# main-power.net
KiCad netlist of a schematic drawn in Altium Designer
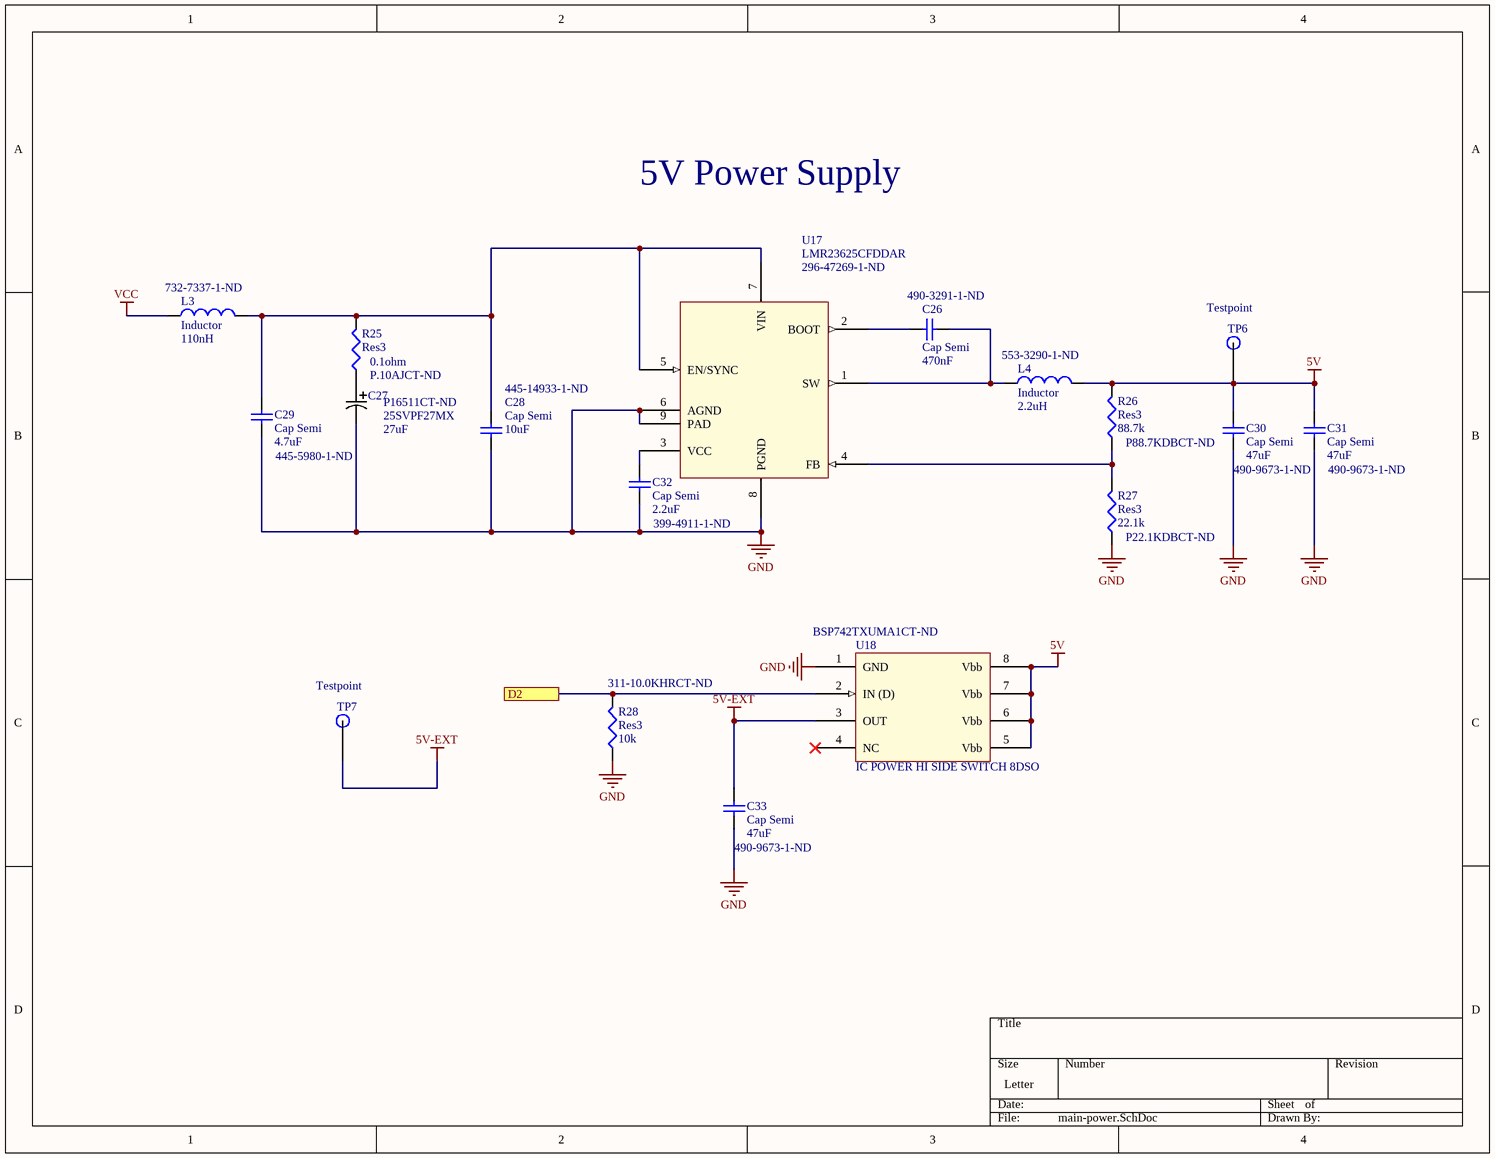
[diagram p0: main-power.SchDoc]

(export (version "E")
  (design (tool "Eeschema 10.0.6"))
  (components
    (comp (ref "C26")
      (value "Cap Semi")
      (footprint "1608[0603]")
      (description "Capacitor (Semiconductor SIM Model)")
      (fields
        (field (name "ALTIUM_VALUE") "470nF")
        (field (name "SUPPLIER PART NUMBER 1") "490-3291-1-ND")
        (field (name "MANUFACTURER") "Murata")
        (field (name "MANUFACTURER PART NUMBER") "GRM188R71E474KA12D")
        (field (name "PUBLISHER") "Altium Limited")
      )
      (libsource (lib "Miscellaneous Devices") (part "Cap Semi"))
    )
    (comp (ref "C27")
      (value "Part Number: 25SVPF27MX")
      (footprint "PCAP_SVP_B6")
      (description "No Description Available")
      (fields
        (field (name "MANUFACTURER_PART_NUMBER") "25SVPF27MX")
        (field (name "SUPPLIER PART NUMBER 1") "P16511CT-ND")
        (field (name "MANUFACTURER") "Panasonic")
        (field (name "MANUFACTURER PART NUMBER") "25SVPF27MX")
        (field (name "CAPACITANCE") "27uF")
        (field (name "COPYRIGHT") "Copyright (C) 2018 Accelerated Designs. All rights reserved")
      )
      (libsource (lib "Panasonic") (part "25SVPF27MX"))
    )
    (comp (ref "C28")
      (value "Cap Semi")
      (footprint "1210")
      (description "Capacitor (Semiconductor SIM Model)")
      (fields
        (field (name "ALTIUM_VALUE") "10uF")
        (field (name "SUPPLIER PART NUMBER 1") "445-14933-1-ND")
        (field (name "MANUFACTURER") "TDK")
        (field (name "MANUFACTURER PART NUMBER") "C3225X7R1H106M250AC")
        (field (name "PUBLISHER") "Altium Limited")
      )
      (libsource (lib "Miscellaneous Devices") (part "Cap Semi"))
    )
    (comp (ref "C29")
      (value "Cap Semi")
      (footprint "0805C")
      (description "Capacitor (Semiconductor SIM Model)")
      (fields
        (field (name "ALTIUM_VALUE") "4.7uF")
        (field (name "SUPPLIER PART NUMBER 1") "445-5980-1-ND")
        (field (name "MANUFACTURER") "TDK")
        (field (name "MANUFACTURER PART NUMBER") "C2012X5R1H475K125AB")
        (field (name "PUBLISHER") "Altium Limited")
      )
      (libsource (lib "Miscellaneous Devices") (part "Cap Semi"))
    )
    (comp (ref "C30")
      (value "Cap Semi")
      (footprint "C1206")
      (description "Capacitor (Semiconductor SIM Model)")
      (fields
        (field (name "ALTIUM_VALUE") "47uF")
        (field (name "SUPPLIER PART NUMBER 1") "490-9673-1-ND")
        (field (name "MANUFACTURER") "Murata")
        (field (name "MANUFACTURER PART NUMBER") "GRM31CR61A476KE15L")
        (field (name "PUBLISHER") "Altium Limited")
      )
      (libsource (lib "Miscellaneous Devices") (part "Cap Semi"))
    )
    (comp (ref "C31")
      (value "Cap Semi")
      (footprint "C1206")
      (description "Capacitor (Semiconductor SIM Model)")
      (fields
        (field (name "ALTIUM_VALUE") "47uF")
        (field (name "SUPPLIER PART NUMBER 1") "490-9673-1-ND")
        (field (name "MANUFACTURER") "Murata")
        (field (name "MANUFACTURER PART NUMBER") "GRM31CR61A476KE15L")
        (field (name "PUBLISHER") "Altium Limited")
      )
      (libsource (lib "Miscellaneous Devices") (part "Cap Semi"))
    )
    (comp (ref "C32")
      (value "Cap Semi")
      (footprint "1608[0603]")
      (description "Capacitor (Semiconductor SIM Model)")
      (fields
        (field (name "ALTIUM_VALUE") "2.2uF")
        (field (name "SUPPLIER PART NUMBER 1") "399-4911-1-ND")
        (field (name "MANUFACTURER") "KEMET")
        (field (name "MANUFACTURER PART NUMBER") "C0603C225K8PACTU")
        (field (name "PUBLISHER") "Altium Limited")
      )
      (libsource (lib "Miscellaneous Devices") (part "Cap Semi"))
    )
    (comp (ref "C33")
      (value "Cap Semi")
      (footprint "C1206")
      (description "Capacitor (Semiconductor SIM Model)")
      (fields
        (field (name "ALTIUM_VALUE") "47uF")
        (field (name "SUPPLIER PART NUMBER 1") "490-9673-1-ND")
        (field (name "MANUFACTURER") "Murata")
        (field (name "MANUFACTURER PART NUMBER") "GRM31CR61A476KE15L")
        (field (name "PUBLISHER") "Altium Limited")
      )
      (libsource (lib "Miscellaneous Devices") (part "Cap Semi"))
    )
    (comp (ref "L3")
      (value "Inductor")
      (footprint "inductor:74479899111")
      (fields
        (field (name "ALTIUM_VALUE") "110nH")
        (field (name "SUPPLIER PART NUMBER 1") "732-7337-1-ND")
        (field (name "MANUFACTURER") "Wurth Electronics")
        (field (name "MANUFACTURER PART NUMBER") "74479899111")
        (field (name "TOLERANCE") "20%")
        (field (name "PUBLISHER") "Altium Limited")
      )
      (libsource (lib "Miscellaneous Devices") (part "Inductor"))
    )
    (comp (ref "L4")
      (value "Inductor")
      (footprint "PA4332.222NLT")
      (fields
        (field (name "ALTIUM_VALUE") "2.2uH")
        (field (name "SUPPLIER PART NUMBER 1") "553-3290-1-ND")
        (field (name "MANUFACTURER") "Pulse Electronics")
        (field (name "MANUFACTURER PART NUMBER") "PA4332.222NLT")
        (field (name "TOLERANCE") "20%")
        (field (name "PUBLISHER") "Altium Limited")
      )
      (libsource (lib "Miscellaneous Devices") (part "Inductor"))
    )
    (comp (ref "R25")
      (value "Res3")
      (footprint "J1-0603")
      (description "Resistor")
      (fields
        (field (name "ALTIUM_VALUE") "0.1ohm")
        (field (name "SUPPLIER PART NUMBER 1") "P.10AJCT-ND")
        (field (name "MANUFACTURER") "Panasonic")
        (field (name "MANUFACTURER PART NUMBER") "ERJ3RSFR10V")
        (field (name "PUBLISHER") "Altium Limited")
      )
      (libsource (lib "Miscellaneous Devices") (part "Res3"))
    )
    (comp (ref "R26")
      (value "Res3")
      (footprint "J1-0603")
      (description "Resistor")
      (fields
        (field (name "ALTIUM_VALUE") "88.7k")
        (field (name "SUPPLIER PART NUMBER 1") "P88.7KDBCT-ND")
        (field (name "MANUFACTURER") "Panasonic")
        (field (name "MANUFACTURER PART NUMBER") "ERA3AEB8872V")
        (field (name "PUBLISHER") "Altium Limited")
      )
      (libsource (lib "Miscellaneous Devices") (part "Res3"))
    )
    (comp (ref "R27")
      (value "Res3")
      (footprint "J1-0603")
      (description "Resistor")
      (fields
        (field (name "ALTIUM_VALUE") "22.1k")
        (field (name "SUPPLIER PART NUMBER 1") "P22.1KDBCT-ND")
        (field (name "MANUFACTURER") "Panasonic")
        (field (name "MANUFACTURER PART NUMBER") "ERA-3AEB2212V")
        (field (name "PUBLISHER") "Altium Limited")
      )
      (libsource (lib "Miscellaneous Devices") (part "Res3"))
    )
    (comp (ref "R28")
      (value "Res3")
      (footprint "J1-0603")
      (description "Resistor")
      (fields
        (field (name "ALTIUM_VALUE") "10k")
        (field (name "SUPPLIER PART NUMBER 1") "311-10.0KHRCT-ND")
        (field (name "MANUFACTURER") "Yageo")
        (field (name "MANUFACTURER PART NUMBER") "RC0603FR-0710KL")
        (field (name "PUBLISHER") "Altium Limited")
      )
      (libsource (lib "Miscellaneous Devices") (part "Res3"))
    )
    (comp (ref "TP6")
      (value "Testpoint")
      (footprint "testpoint")
      (description "SMT Testpoint")
      (libsource (lib "testpoints") (part "SMT Testpoint"))
    )
    (comp (ref "TP7")
      (value "Testpoint")
      (footprint "testpoint")
      (description "SMT Testpoint")
      (libsource (lib "testpoints") (part "SMT Testpoint"))
    )
    (comp (ref "U17")
      (value "LMR23625CFDDAR")
      (footprint "DDA0008E_L")
      (fields
        (field (name "SUPPLIER PART NUMBER 1") "296-47269-1-ND")
        (field (name "MANUFACTURER") "Texas Instruments")
      )
      (libsource (lib "ti") (part "LMR23625CFDDAR"))
    )
    (comp (ref "U18")
      (value "IC POWER HI SIDE SWITCH 8DSO")
      (footprint "SOIC127P600-8N")
      (fields
        (field (name "SUPPLIER PART NUMBER 1") "BSP742TXUMA1CT-ND")
        (field (name "MANUFACTURER") "Infineon")
        (field (name "MANUFACTURER PART NUMBER") "BSP742TXUMA1")
      )
      (libsource (lib "Infineon") (part "BSP742TXUMA1"))
    )
  )
  (nets
    (net (code "1") (name "/D2") (class "Default")
      (node (ref "R28") (pin "2") (pinfunction "2_2") (pintype "passive"))
      (node (ref "U18") (pin "2") (pinfunction "IN_(D)_2") (pintype "input"))
    )
    (net (code "2") (name "5V") (class "Default")
      (node (ref "C30") (pin "2") (pinfunction "2_2") (pintype "passive"))
      (node (ref "C31") (pin "2") (pinfunction "2_2") (pintype "passive"))
      (node (ref "L4") (pin "2") (pinfunction "2_2") (pintype "passive"))
      (node (ref "R26") (pin "2") (pinfunction "2_2") (pintype "passive"))
      (node (ref "TP6") (pin "1") (pinfunction "1_1") (pintype "passive"))
      (node (ref "U18") (pin "5") (pinfunction "Vbb_5") (pintype "power_in"))
      (node (ref "U18") (pin "6") (pinfunction "Vbb_6") (pintype "power_in"))
      (node (ref "U18") (pin "7") (pinfunction "Vbb_7") (pintype "power_in"))
      (node (ref "U18") (pin "8") (pinfunction "Vbb_8") (pintype "power_in"))
    )
    (net (code "3") (name "5V-EXT") (class "Default")
      (node (ref "C33") (pin "2") (pinfunction "2_2") (pintype "passive"))
      (node (ref "TP7") (pin "1") (pinfunction "1_1") (pintype "passive"))
      (node (ref "U18") (pin "3") (pinfunction "OUT_3") (pintype "power_in"))
    )
    (net (code "4") (name "GND") (class "Default")
      (node (ref "C27") (pin "2") (pinfunction "2_2") (pintype "passive"))
      (node (ref "C28") (pin "1") (pinfunction "1_1") (pintype "passive"))
      (node (ref "C29") (pin "1") (pinfunction "1_1") (pintype "passive"))
      (node (ref "C30") (pin "1") (pinfunction "1_1") (pintype "passive"))
      (node (ref "C31") (pin "1") (pinfunction "1_1") (pintype "passive"))
      (node (ref "C32") (pin "1") (pinfunction "1_1") (pintype "passive"))
      (node (ref "C33") (pin "1") (pinfunction "1_1") (pintype "passive"))
      (node (ref "R27") (pin "1") (pinfunction "1_1") (pintype "passive"))
      (node (ref "R28") (pin "1") (pinfunction "1_1") (pintype "passive"))
      (node (ref "U17") (pin "6") (pinfunction "AGND_6") (pintype "power_in"))
      (node (ref "U17") (pin "8") (pinfunction "PGND_8") (pintype "power_in"))
      (node (ref "U17") (pin "9") (pinfunction "PAD_9") (pintype "power_in"))
      (node (ref "U18") (pin "1") (pinfunction "GND_1") (pintype "power_in"))
    )
    (net (code "5") (name "Net-(C27-Pad1)") (class "Default")
      (node (ref "C27") (pin "1") (pinfunction "1_1") (pintype "passive"))
      (node (ref "R25") (pin "1") (pinfunction "1_1") (pintype "passive"))
    )
    (net (code "6") (name "Net-(U17-BOOT)") (class "Default")
      (node (ref "C26") (pin "1") (pinfunction "1_1") (pintype "passive"))
      (node (ref "U17") (pin "2") (pinfunction "BOOT_2") (pintype "output"))
    )
    (net (code "7") (name "Net-(U17-EN{slash}SYNC)") (class "Default")
      (node (ref "C28") (pin "2") (pinfunction "2_2") (pintype "passive"))
      (node (ref "C29") (pin "2") (pinfunction "2_2") (pintype "passive"))
      (node (ref "L3") (pin "2") (pinfunction "2_2") (pintype "passive"))
      (node (ref "R25") (pin "2") (pinfunction "2_2") (pintype "passive"))
      (node (ref "U17") (pin "5") (pinfunction "EN/SYNC_5") (pintype "input"))
      (node (ref "U17") (pin "7") (pinfunction "VIN_7") (pintype "power_in"))
    )
    (net (code "8") (name "Net-(U17-FB)") (class "Default")
      (node (ref "R26") (pin "1") (pinfunction "1_1") (pintype "passive"))
      (node (ref "R27") (pin "2") (pinfunction "2_2") (pintype "passive"))
      (node (ref "U17") (pin "4") (pinfunction "FB_4") (pintype "input"))
    )
    (net (code "9") (name "Net-(U17-SW)") (class "Default")
      (node (ref "C26") (pin "2") (pinfunction "2_2") (pintype "passive"))
      (node (ref "L4") (pin "1") (pinfunction "1_1") (pintype "passive"))
      (node (ref "U17") (pin "1") (pinfunction "SW_1") (pintype "output"))
    )
    (net (code "10") (name "Net-(U17-VCC)") (class "Default")
      (node (ref "C32") (pin "2") (pinfunction "2_2") (pintype "passive"))
      (node (ref "U17") (pin "3") (pinfunction "VCC_3") (pintype "power_in"))
    )
    (net (code "11") (name "VCC") (class "Default")
      (node (ref "L3") (pin "1") (pinfunction "1_1") (pintype "passive"))
    )
    (net (code "12") (name "unconnected-(U18-NC-Pad4)") (class "Default")
      (node (ref "U18") (pin "4") (pinfunction "NC_4") (pintype "passive+no_connect"))
    )
  )
)
